# OMD_Fets_40A.net
KiCad netlist of a schematic drawn in Altium Designer
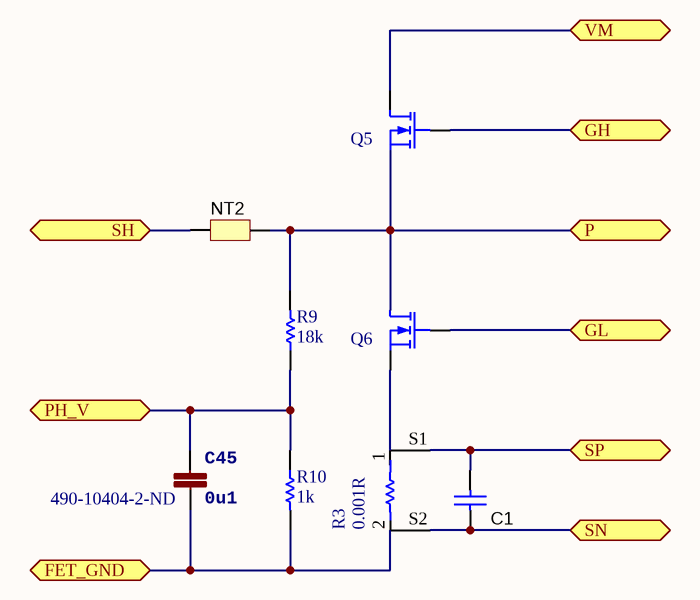
[diagram p0: OMD_Fets_40A.SchDoc]

(export (version "E")
  (design (tool "Eeschema 10.0.6"))
  (components
    (comp (ref "C1")
      (value "~")
      (footprint "0603-CAP")
      (description "CAP, CERM, 1000pF, 16V, +/-10%, X7R, 0603")
      (libsource (lib "OMD") (part "GRM188R71C102KA01D"))
    )
    (comp (ref "C45")
      (value "0u1")
      (footprint "0201-cap")
      (description "CAP CER 0.1UF 6V Y5V 0201")
      (fields (field (name "SUPPLIER PART NUMBER 1") "490-10404-2-ND"))
      (libsource (lib "OMD") (part "CAP0402"))
    )
    (comp (ref "NT2")
      (value "Net-Tie")
      (footprint "Net-Tie_10mil")
      (description "Single point connection between nets.")
      (libsource (lib "OMD") (part "Net-Tie"))
    )
    (comp (ref "Q5")
      (value "MOSFET-N")
      (footprint "Q5B")
      (description "N-Channel MOSFET")
      (libsource (lib "") (part "MOSFET-N_1"))
    )
    (comp (ref "Q6")
      (value "MOSFET-N")
      (footprint "Q5B")
      (description "N-Channel MOSFET")
      (libsource (lib "OMD") (part "MOSFET-N"))
    )
    (comp (ref "R3")
      (value "0.001R")
      (footprint "4RESC5125X09N")
      (description "2W, 0.001R 5025 current sense resistor")
      (fields (field (name "Comment") "Current sense resistor"))
      (libsource (lib "OMD") (part "WSLP20101L000FEK"))
    )
    (comp (ref "R9")
      (value "18k")
      (footprint "R0805")
      (description "RES SMD 18K OHM 1% 1/8W 0805")
      (fields (field (name "Comment") "RES"))
      (libsource (lib "OMD") (part "RES"))
    )
    (comp (ref "R10")
      (value "1k")
      (footprint "R0805")
      (description "RES SMD 1K OHM 1% 1/8W 0805")
      (fields (field (name "Comment") "RES"))
      (libsource (lib "OMD") (part "RES"))
    )
  )
  (nets
    (net (code "1") (name "/FET_GND") (class "Default")
      (node (ref "C45") (pin "2") (pinfunction "2_2") (pintype "passive"))
      (node (ref "R10") (pin "2") (pinfunction "2_2") (pintype "passive"))
      (node (ref "R3") (pin "2") (pinfunction "2_2") (pintype "passive"))
    )
    (net (code "2") (name "/GH") (class "Default")
      (node (ref "Q5") (pin "G") (pinfunction "G_G") (pintype "passive"))
    )
    (net (code "3") (name "/GL") (class "Default")
      (node (ref "Q6") (pin "G") (pinfunction "G_G") (pintype "passive"))
    )
    (net (code "4") (name "/P") (class "Default")
      (node (ref "NT2") (pin "2") (pinfunction "2_2") (pintype "passive"))
      (node (ref "Q5") (pin "S") (pinfunction "S_S") (pintype "passive"))
      (node (ref "Q6") (pin "D") (pinfunction "D_D") (pintype "passive"))
      (node (ref "R9") (pin "2") (pinfunction "2_2") (pintype "passive"))
    )
    (net (code "5") (name "/PH_V") (class "Default")
      (node (ref "C45") (pin "1") (pinfunction "1_1") (pintype "passive"))
      (node (ref "R10") (pin "1") (pinfunction "1_1") (pintype "passive"))
      (node (ref "R9") (pin "1") (pinfunction "1_1") (pintype "passive"))
    )
    (net (code "6") (name "/SH") (class "Default")
      (node (ref "NT2") (pin "1") (pinfunction "1_1") (pintype "passive"))
    )
    (net (code "7") (name "/SN") (class "Default")
      (node (ref "C1") (pin "2") (pinfunction "2_2") (pintype "passive"))
      (node (ref "R3") (pin "S2") (pinfunction "S2_S2") (pintype "passive"))
    )
    (net (code "8") (name "/SP") (class "Default")
      (node (ref "C1") (pin "1") (pinfunction "1_1") (pintype "passive"))
      (node (ref "R3") (pin "S1") (pinfunction "S1_S1") (pintype "passive"))
    )
    (net (code "9") (name "/VM") (class "Default")
      (node (ref "Q5") (pin "D") (pinfunction "D_D") (pintype "passive"))
    )
    (net (code "10") (name "Net-(Q6-PadS)") (class "Default")
      (node (ref "Q6") (pin "S") (pinfunction "S_S") (pintype "passive"))
      (node (ref "R3") (pin "1") (pinfunction "1_1") (pintype "passive"))
    )
  )
)
